# iF11L.net
KiCad netlist of a schematic drawn in Altium Designer
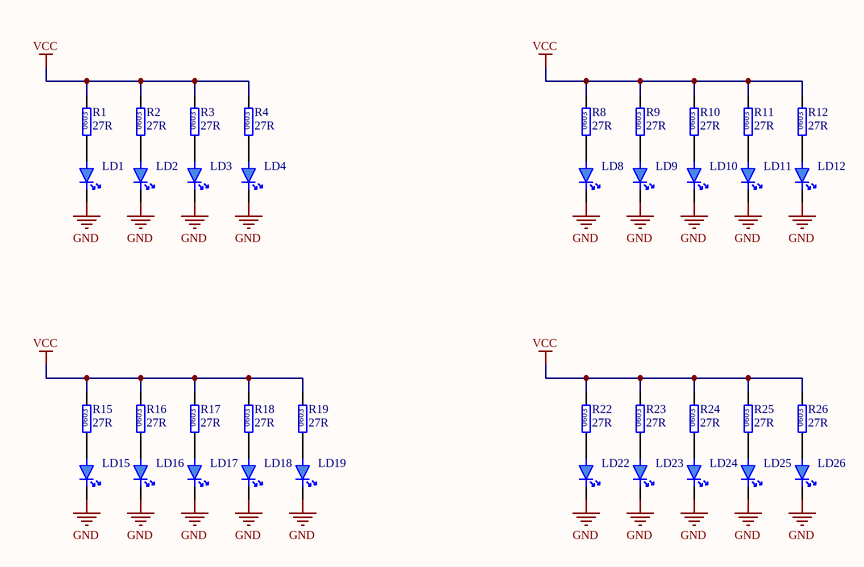
[diagram p0: iF11L.SchDoc]

(export (version "E")
  (design (tool "Eeschema 10.0.6"))
  (components
    (comp (ref "LD1")
      (value "HQ19-2101UWCE2 0603")
      (footprint "LED-0603-WS")
      (libsource (lib "Optoelectronics") (part "LED WS"))
    )
    (comp (ref "LD2")
      (value "HQ19-2101UWCE2 0603")
      (footprint "LED-0603-WS")
      (libsource (lib "Optoelectronics") (part "LED WS"))
    )
    (comp (ref "LD3")
      (value "HQ19-2101UWCE2 0603")
      (footprint "LED-0603-WS")
      (libsource (lib "Optoelectronics") (part "LED WS"))
    )
    (comp (ref "LD4")
      (value "HQ19-2101UWCE2 0603")
      (footprint "LED-0603-WS")
      (libsource (lib "Optoelectronics") (part "LED WS"))
    )
    (comp (ref "LD8")
      (value "HQ19-2101UWCE2 0603")
      (footprint "LED-0603-WS")
      (libsource (lib "Optoelectronics") (part "LED WS"))
    )
    (comp (ref "LD9")
      (value "HQ19-2101UWCE2 0603")
      (footprint "LED-0603-WS")
      (libsource (lib "Optoelectronics") (part "LED WS"))
    )
    (comp (ref "LD10")
      (value "HQ19-2101UWCE2 0603")
      (footprint "LED-0603-WS")
      (libsource (lib "Optoelectronics") (part "LED WS"))
    )
    (comp (ref "LD11")
      (value "HQ19-2101UWCE2 0603")
      (footprint "LED-0603-WS")
      (libsource (lib "Optoelectronics") (part "LED WS"))
    )
    (comp (ref "LD12")
      (value "HQ19-2101UWCE2 0603")
      (footprint "LED-0603-WS")
      (libsource (lib "Optoelectronics") (part "LED WS"))
    )
    (comp (ref "LD15")
      (value "HQ19-2101UWCE2 0603")
      (footprint "LED-0603-WS")
      (libsource (lib "Optoelectronics") (part "LED WS"))
    )
    (comp (ref "LD16")
      (value "HQ19-2101UWCE2 0603")
      (footprint "LED-0603-WS")
      (libsource (lib "Optoelectronics") (part "LED WS"))
    )
    (comp (ref "LD17")
      (value "HQ19-2101UWCE2 0603")
      (footprint "LED-0603-WS")
      (libsource (lib "Optoelectronics") (part "LED WS"))
    )
    (comp (ref "LD18")
      (value "HQ19-2101UWCE2 0603")
      (footprint "LED-0603-WS")
      (libsource (lib "Optoelectronics") (part "LED WS"))
    )
    (comp (ref "LD19")
      (value "HQ19-2101UWCE2 0603")
      (footprint "LED-0603-WS")
      (libsource (lib "Optoelectronics") (part "LED WS"))
    )
    (comp (ref "LD22")
      (value "HQ19-2101UWCE2 0603")
      (footprint "LED-0603-WS")
      (libsource (lib "Optoelectronics") (part "LED WS"))
    )
    (comp (ref "LD23")
      (value "HQ19-2101UWCE2 0603")
      (footprint "LED-0603-WS")
      (libsource (lib "Optoelectronics") (part "LED WS"))
    )
    (comp (ref "LD24")
      (value "HQ19-2101UWCE2 0603")
      (footprint "LED-0603-WS")
      (libsource (lib "Optoelectronics") (part "LED WS"))
    )
    (comp (ref "LD25")
      (value "HQ19-2101UWCE2 0603")
      (footprint "LED-0603-WS")
      (libsource (lib "Optoelectronics") (part "LED WS"))
    )
    (comp (ref "LD26")
      (value "HQ19-2101UWCE2 0603")
      (footprint "LED-0603-WS")
      (libsource (lib "Optoelectronics") (part "LED WS"))
    )
    (comp (ref "R1")
      (value "27R")
      (footprint "R0603-LD")
      (description "5%")
      (fields (field (name "PART NO") "W-T-RE-RS03K270JT") (field (name "MANUFACTURER") "LAGEO"))
      (libsource (lib "Rescap") (part "R 0603 27R"))
    )
    (comp (ref "R2")
      (value "27R")
      (footprint "R0603-LD")
      (description "5%")
      (fields (field (name "PART NO") "W-T-RE-RS03K270JT") (field (name "MANUFACTURER") "LAGEO"))
      (libsource (lib "Rescap") (part "R 0603 27R"))
    )
    (comp (ref "R3")
      (value "27R")
      (footprint "R0603-LD")
      (description "5%")
      (fields (field (name "PART NO") "W-T-RE-RS03K270JT") (field (name "MANUFACTURER") "LAGEO"))
      (libsource (lib "Rescap") (part "R 0603 27R"))
    )
    (comp (ref "R4")
      (value "27R")
      (footprint "R0603-LD")
      (description "5%")
      (fields (field (name "PART NO") "W-T-RE-RS03K270JT") (field (name "MANUFACTURER") "LAGEO"))
      (libsource (lib "Rescap") (part "R 0603 27R"))
    )
    (comp (ref "R8")
      (value "27R")
      (footprint "R0603-LD")
      (description "5%")
      (fields (field (name "PART NO") "W-T-RE-RS03K270JT") (field (name "MANUFACTURER") "LAGEO"))
      (libsource (lib "Rescap") (part "R 0603 27R"))
    )
    (comp (ref "R9")
      (value "27R")
      (footprint "R0603-LD")
      (description "5%")
      (fields (field (name "PART NO") "W-T-RE-RS03K270JT") (field (name "MANUFACTURER") "LAGEO"))
      (libsource (lib "Rescap") (part "R 0603 27R"))
    )
    (comp (ref "R10")
      (value "27R")
      (footprint "R0603-LD")
      (description "5%")
      (fields (field (name "PART NO") "W-T-RE-RS03K270JT") (field (name "MANUFACTURER") "LAGEO"))
      (libsource (lib "Rescap") (part "R 0603 27R"))
    )
    (comp (ref "R11")
      (value "27R")
      (footprint "R0603-LD")
      (description "5%")
      (fields (field (name "PART NO") "W-T-RE-RS03K270JT") (field (name "MANUFACTURER") "LAGEO"))
      (libsource (lib "Rescap") (part "R 0603 27R"))
    )
    (comp (ref "R12")
      (value "27R")
      (footprint "R0603-LD")
      (description "5%")
      (fields (field (name "PART NO") "W-T-RE-RS03K270JT") (field (name "MANUFACTURER") "LAGEO"))
      (libsource (lib "Rescap") (part "R 0603 27R"))
    )
    (comp (ref "R15")
      (value "27R")
      (footprint "R0603-LD")
      (description "5%")
      (fields (field (name "PART NO") "W-T-RE-RS03K270JT") (field (name "MANUFACTURER") "LAGEO"))
      (libsource (lib "Rescap") (part "R 0603 27R"))
    )
    (comp (ref "R16")
      (value "27R")
      (footprint "R0603-LD")
      (description "5%")
      (fields (field (name "PART NO") "W-T-RE-RS03K270JT") (field (name "MANUFACTURER") "LAGEO"))
      (libsource (lib "Rescap") (part "R 0603 27R"))
    )
    (comp (ref "R17")
      (value "27R")
      (footprint "R0603-LD")
      (description "5%")
      (fields (field (name "PART NO") "W-T-RE-RS03K270JT") (field (name "MANUFACTURER") "LAGEO"))
      (libsource (lib "Rescap") (part "R 0603 27R"))
    )
    (comp (ref "R18")
      (value "27R")
      (footprint "R0603-LD")
      (description "5%")
      (fields (field (name "PART NO") "W-T-RE-RS03K270JT") (field (name "MANUFACTURER") "LAGEO"))
      (libsource (lib "Rescap") (part "R 0603 27R"))
    )
    (comp (ref "R19")
      (value "27R")
      (footprint "R0603-LD")
      (description "5%")
      (fields (field (name "PART NO") "W-T-RE-RS03K270JT") (field (name "MANUFACTURER") "LAGEO"))
      (libsource (lib "Rescap") (part "R 0603 27R"))
    )
    (comp (ref "R22")
      (value "27R")
      (footprint "R0603-LD")
      (description "5%")
      (fields (field (name "PART NO") "W-T-RE-RS03K270JT") (field (name "MANUFACTURER") "LAGEO"))
      (libsource (lib "Rescap") (part "R 0603 27R"))
    )
    (comp (ref "R23")
      (value "27R")
      (footprint "R0603-LD")
      (description "5%")
      (fields (field (name "PART NO") "W-T-RE-RS03K270JT") (field (name "MANUFACTURER") "LAGEO"))
      (libsource (lib "Rescap") (part "R 0603 27R"))
    )
    (comp (ref "R24")
      (value "27R")
      (footprint "R0603-LD")
      (description "5%")
      (fields (field (name "PART NO") "W-T-RE-RS03K270JT") (field (name "MANUFACTURER") "LAGEO"))
      (libsource (lib "Rescap") (part "R 0603 27R"))
    )
    (comp (ref "R25")
      (value "27R")
      (footprint "R0603-LD")
      (description "5%")
      (fields (field (name "PART NO") "W-T-RE-RS03K270JT") (field (name "MANUFACTURER") "LAGEO"))
      (libsource (lib "Rescap") (part "R 0603 27R"))
    )
    (comp (ref "R26")
      (value "27R")
      (footprint "R0603-LD")
      (description "5%")
      (fields (field (name "PART NO") "W-T-RE-RS03K270JT") (field (name "MANUFACTURER") "LAGEO"))
      (libsource (lib "Rescap") (part "R 0603 27R"))
    )
  )
  (nets
    (net (code "1") (name "GND") (class "Default")
      (node (ref "LD1") (pin "2") (pinfunction "K_2") (pintype "passive"))
      (node (ref "LD10") (pin "2") (pinfunction "K_2") (pintype "passive"))
      (node (ref "LD11") (pin "2") (pinfunction "K_2") (pintype "passive"))
      (node (ref "LD12") (pin "2") (pinfunction "K_2") (pintype "passive"))
      (node (ref "LD15") (pin "2") (pinfunction "K_2") (pintype "passive"))
      (node (ref "LD16") (pin "2") (pinfunction "K_2") (pintype "passive"))
      (node (ref "LD17") (pin "2") (pinfunction "K_2") (pintype "passive"))
      (node (ref "LD18") (pin "2") (pinfunction "K_2") (pintype "passive"))
      (node (ref "LD19") (pin "2") (pinfunction "K_2") (pintype "passive"))
      (node (ref "LD2") (pin "2") (pinfunction "K_2") (pintype "passive"))
      (node (ref "LD22") (pin "2") (pinfunction "K_2") (pintype "passive"))
      (node (ref "LD23") (pin "2") (pinfunction "K_2") (pintype "passive"))
      (node (ref "LD24") (pin "2") (pinfunction "K_2") (pintype "passive"))
      (node (ref "LD25") (pin "2") (pinfunction "K_2") (pintype "passive"))
      (node (ref "LD26") (pin "2") (pinfunction "K_2") (pintype "passive"))
      (node (ref "LD3") (pin "2") (pinfunction "K_2") (pintype "passive"))
      (node (ref "LD4") (pin "2") (pinfunction "K_2") (pintype "passive"))
      (node (ref "LD8") (pin "2") (pinfunction "K_2") (pintype "passive"))
      (node (ref "LD9") (pin "2") (pinfunction "K_2") (pintype "passive"))
    )
    (net (code "2") (name "Net-(LD1-A)") (class "Default")
      (node (ref "LD1") (pin "1") (pinfunction "A_1") (pintype "passive"))
      (node (ref "R1") (pin "1") (pinfunction "1_1") (pintype "passive"))
    )
    (net (code "3") (name "Net-(LD2-A)") (class "Default")
      (node (ref "LD2") (pin "1") (pinfunction "A_1") (pintype "passive"))
      (node (ref "R2") (pin "1") (pinfunction "1_1") (pintype "passive"))
    )
    (net (code "4") (name "Net-(LD3-A)") (class "Default")
      (node (ref "LD3") (pin "1") (pinfunction "A_1") (pintype "passive"))
      (node (ref "R3") (pin "1") (pinfunction "1_1") (pintype "passive"))
    )
    (net (code "5") (name "Net-(LD4-A)") (class "Default")
      (node (ref "LD4") (pin "1") (pinfunction "A_1") (pintype "passive"))
      (node (ref "R4") (pin "1") (pinfunction "1_1") (pintype "passive"))
    )
    (net (code "6") (name "Net-(LD8-A)") (class "Default")
      (node (ref "LD8") (pin "1") (pinfunction "A_1") (pintype "passive"))
      (node (ref "R8") (pin "1") (pinfunction "1_1") (pintype "passive"))
    )
    (net (code "7") (name "Net-(LD9-A)") (class "Default")
      (node (ref "LD9") (pin "1") (pinfunction "A_1") (pintype "passive"))
      (node (ref "R9") (pin "1") (pinfunction "1_1") (pintype "passive"))
    )
    (net (code "8") (name "Net-(LD10-A)") (class "Default")
      (node (ref "LD10") (pin "1") (pinfunction "A_1") (pintype "passive"))
      (node (ref "R10") (pin "1") (pinfunction "1_1") (pintype "passive"))
    )
    (net (code "9") (name "Net-(LD11-A)") (class "Default")
      (node (ref "LD11") (pin "1") (pinfunction "A_1") (pintype "passive"))
      (node (ref "R11") (pin "1") (pinfunction "1_1") (pintype "passive"))
    )
    (net (code "10") (name "Net-(LD12-A)") (class "Default")
      (node (ref "LD12") (pin "1") (pinfunction "A_1") (pintype "passive"))
      (node (ref "R12") (pin "1") (pinfunction "1_1") (pintype "passive"))
    )
    (net (code "11") (name "Net-(LD15-A)") (class "Default")
      (node (ref "LD15") (pin "1") (pinfunction "A_1") (pintype "passive"))
      (node (ref "R15") (pin "1") (pinfunction "1_1") (pintype "passive"))
    )
    (net (code "12") (name "Net-(LD16-A)") (class "Default")
      (node (ref "LD16") (pin "1") (pinfunction "A_1") (pintype "passive"))
      (node (ref "R16") (pin "1") (pinfunction "1_1") (pintype "passive"))
    )
    (net (code "13") (name "Net-(LD17-A)") (class "Default")
      (node (ref "LD17") (pin "1") (pinfunction "A_1") (pintype "passive"))
      (node (ref "R17") (pin "1") (pinfunction "1_1") (pintype "passive"))
    )
    (net (code "14") (name "Net-(LD18-A)") (class "Default")
      (node (ref "LD18") (pin "1") (pinfunction "A_1") (pintype "passive"))
      (node (ref "R18") (pin "1") (pinfunction "1_1") (pintype "passive"))
    )
    (net (code "15") (name "Net-(LD19-A)") (class "Default")
      (node (ref "LD19") (pin "1") (pinfunction "A_1") (pintype "passive"))
      (node (ref "R19") (pin "1") (pinfunction "1_1") (pintype "passive"))
    )
    (net (code "16") (name "Net-(LD22-A)") (class "Default")
      (node (ref "LD22") (pin "1") (pinfunction "A_1") (pintype "passive"))
      (node (ref "R22") (pin "1") (pinfunction "1_1") (pintype "passive"))
    )
    (net (code "17") (name "Net-(LD23-A)") (class "Default")
      (node (ref "LD23") (pin "1") (pinfunction "A_1") (pintype "passive"))
      (node (ref "R23") (pin "1") (pinfunction "1_1") (pintype "passive"))
    )
    (net (code "18") (name "Net-(LD24-A)") (class "Default")
      (node (ref "LD24") (pin "1") (pinfunction "A_1") (pintype "passive"))
      (node (ref "R24") (pin "1") (pinfunction "1_1") (pintype "passive"))
    )
    (net (code "19") (name "Net-(LD25-A)") (class "Default")
      (node (ref "LD25") (pin "1") (pinfunction "A_1") (pintype "passive"))
      (node (ref "R25") (pin "1") (pinfunction "1_1") (pintype "passive"))
    )
    (net (code "20") (name "Net-(LD26-A)") (class "Default")
      (node (ref "LD26") (pin "1") (pinfunction "A_1") (pintype "passive"))
      (node (ref "R26") (pin "1") (pinfunction "1_1") (pintype "passive"))
    )
    (net (code "21") (name "VCC") (class "Default")
      (node (ref "R1") (pin "2") (pinfunction "2_2") (pintype "passive"))
      (node (ref "R10") (pin "2") (pinfunction "2_2") (pintype "passive"))
      (node (ref "R11") (pin "2") (pinfunction "2_2") (pintype "passive"))
      (node (ref "R12") (pin "2") (pinfunction "2_2") (pintype "passive"))
      (node (ref "R15") (pin "2") (pinfunction "2_2") (pintype "passive"))
      (node (ref "R16") (pin "2") (pinfunction "2_2") (pintype "passive"))
      (node (ref "R17") (pin "2") (pinfunction "2_2") (pintype "passive"))
      (node (ref "R18") (pin "2") (pinfunction "2_2") (pintype "passive"))
      (node (ref "R19") (pin "2") (pinfunction "2_2") (pintype "passive"))
      (node (ref "R2") (pin "2") (pinfunction "2_2") (pintype "passive"))
      (node (ref "R22") (pin "2") (pinfunction "2_2") (pintype "passive"))
      (node (ref "R23") (pin "2") (pinfunction "2_2") (pintype "passive"))
      (node (ref "R24") (pin "2") (pinfunction "2_2") (pintype "passive"))
      (node (ref "R25") (pin "2") (pinfunction "2_2") (pintype "passive"))
      (node (ref "R26") (pin "2") (pinfunction "2_2") (pintype "passive"))
      (node (ref "R3") (pin "2") (pinfunction "2_2") (pintype "passive"))
      (node (ref "R4") (pin "2") (pinfunction "2_2") (pintype "passive"))
      (node (ref "R8") (pin "2") (pinfunction "2_2") (pintype "passive"))
      (node (ref "R9") (pin "2") (pinfunction "2_2") (pintype "passive"))
    )
  )
)
